# Elektriskeem.net
KiCad netlist of a schematic drawn in Altium Designer
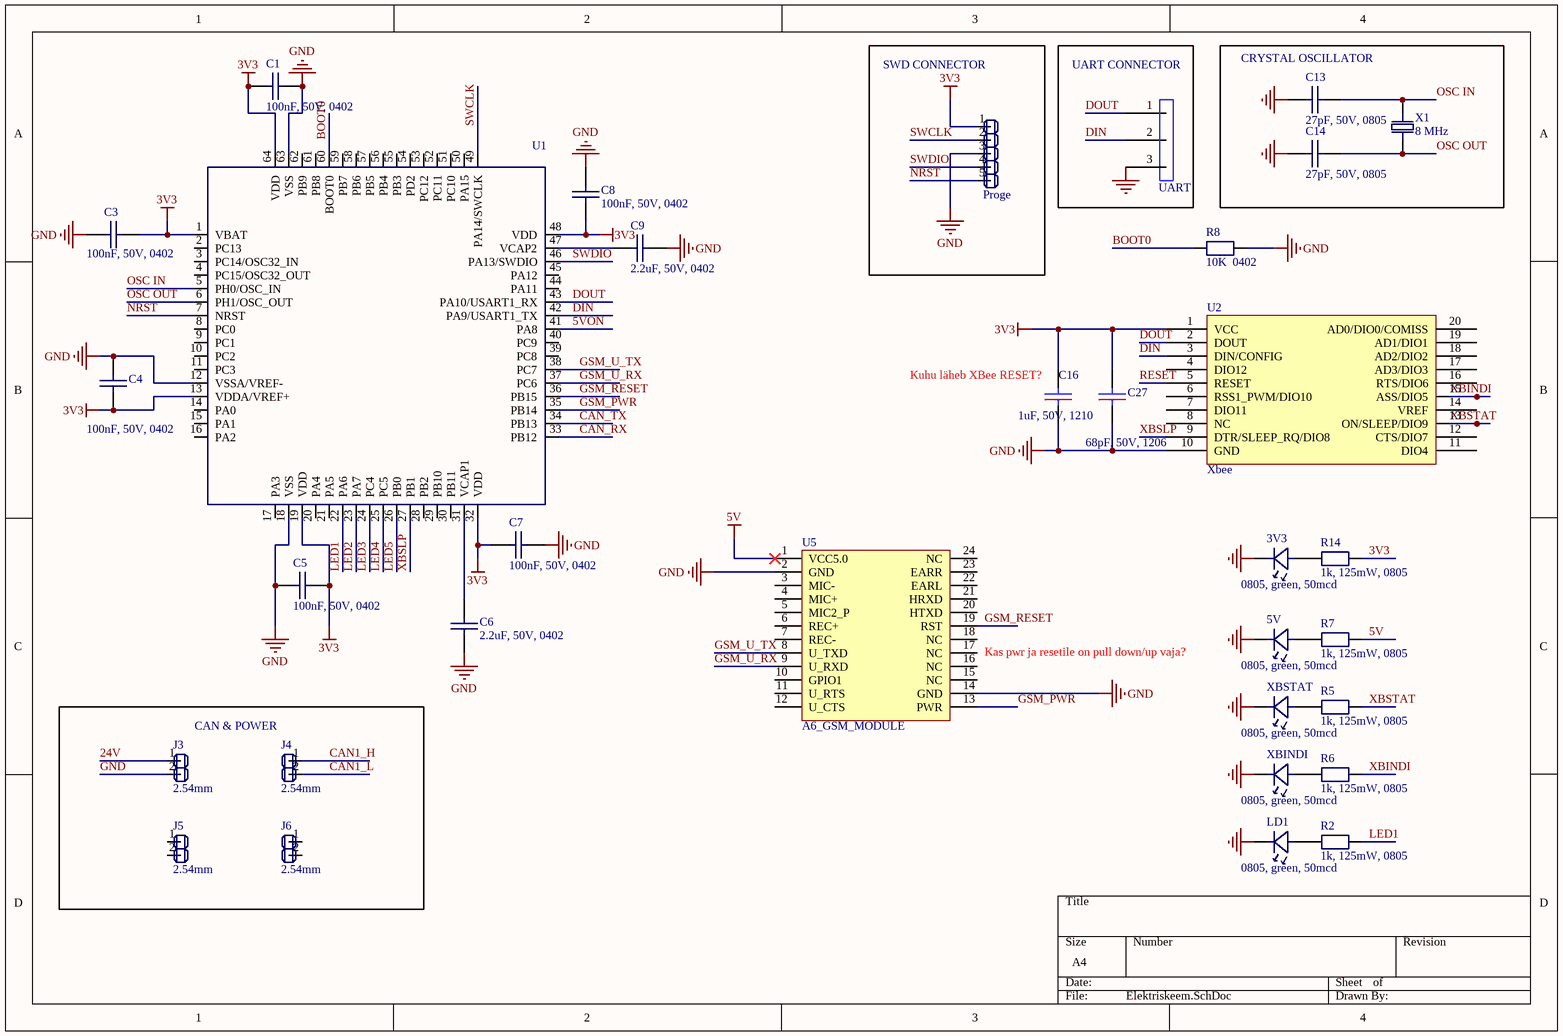
[diagram p0: Elektriskeem.SchDoc]

(export (version "E")
  (design (tool "Eeschema 10.0.6"))
  (components
    (comp (ref "3V3")
      (value "0805, green, 50mcd")
      (footprint "LED2012X06N")
      (description "Cathode (-) marked by silkscreen line")
      (fields (field (name "MANUFACTURER") "KINGBRIGHT"))
      (libsource (lib "AS_component_library") (part "LED"))
    )
    (comp (ref "5V")
      (value "0805, green, 50mcd")
      (footprint "LED2012X06N")
      (description "Cathode (-) marked by silkscreen line")
      (fields (field (name "MANUFACTURER") "KINGBRIGHT"))
      (libsource (lib "AS_component_library") (part "LED"))
    )
    (comp (ref "C1")
      (value "100nF, 50V, 0402")
      (footprint "1005 [0402] CAP")
      (libsource (lib "AS_component_library") (part "Capacitor"))
    )
    (comp (ref "C3")
      (value "100nF, 50V, 0402")
      (footprint "1005 [0402] CAP")
      (libsource (lib "AS_component_library") (part "Capacitor"))
    )
    (comp (ref "C4")
      (value "100nF, 50V, 0402")
      (footprint "1005 [0402] CAP")
      (libsource (lib "AS_component_library") (part "Capacitor"))
    )
    (comp (ref "C5")
      (value "100nF, 50V, 0402")
      (footprint "1005 [0402] CAP")
      (libsource (lib "AS_component_library") (part "Capacitor"))
    )
    (comp (ref "C6")
      (value "2.2uF, 50V, 0402")
      (footprint "1005 [0402] CAP")
      (libsource (lib "AS_component_library") (part "Capacitor"))
    )
    (comp (ref "C7")
      (value "100nF, 50V, 0402")
      (footprint "1005 [0402] CAP")
      (libsource (lib "AS_component_library") (part "Capacitor"))
    )
    (comp (ref "C8")
      (value "100nF, 50V, 0402")
      (footprint "1005 [0402] CAP")
      (libsource (lib "AS_component_library") (part "Capacitor"))
    )
    (comp (ref "C9")
      (value "2.2uF, 50V, 0402")
      (footprint "1005 [0402] CAP")
      (libsource (lib "AS_component_library") (part "Capacitor"))
    )
    (comp (ref "C13")
      (value "27pF, 50V, 0805")
      (footprint "2012 [0805] CAP")
      (fields (field (name "MANUFACTURER") "KEMET"))
      (libsource (lib "AS_component_library") (part "Capacitor"))
    )
    (comp (ref "C14")
      (value "27pF, 50V, 0805")
      (footprint "2012 [0805] CAP")
      (fields (field (name "MANUFACTURER") "KEMET"))
      (libsource (lib "AS_component_library") (part "Capacitor"))
    )
    (comp (ref "C16")
      (value "1uF, 50V, 1210")
      (footprint "3225 [1210] CAP")
      (libsource (lib "AS_component_library") (part "Capacitor"))
    )
    (comp (ref "C27")
      (value "68pF, 50V, 1206")
      (footprint "3216 [1206] CAP")
      (libsource (lib "5VTO3V3") (part "Capacitor"))
    )
    (comp (ref "J3")
      (value "2.54mm")
      (footprint "Pin Header 2x1")
      (libsource (lib "AS_component_library") (part "Pin Header 2x1"))
    )
    (comp (ref "J4")
      (value "2.54mm")
      (footprint "Pin Header 2x1")
      (libsource (lib "AS_component_library") (part "Pin Header 2x1"))
    )
    (comp (ref "J5")
      (value "2.54mm")
      (footprint "Pin Header 2x1")
      (libsource (lib "AS_component_library") (part "Pin Header 2x1"))
    )
    (comp (ref "J6")
      (value "2.54mm")
      (footprint "Pin Header 2x1")
      (libsource (lib "AS_component_library") (part "Pin Header 2x1"))
    )
    (comp (ref "LD1")
      (value "0805, green, 50mcd")
      (footprint "LED2012X06N")
      (description "Cathode (-) marked by silkscreen line")
      (fields (field (name "MANUFACTURER") "KINGBRIGHT"))
      (libsource (lib "AS_component_library") (part "LED"))
    )
    (comp (ref "Proge")
      (value "Pin Header 5x1")
      (footprint "Pin Header 5x1")
      (fields (field (name "MANUFACTURER") "TE CONNECTIVITY"))
      (libsource (lib "AS_component_library") (part "Pin Header 5x1"))
    )
    (comp (ref "R2")
      (value "1k, 125mW, 0805")
      (footprint "2012 [0805] RES")
      (fields (field (name "MANUFACTURER") "VISHAY DRALORIC"))
      (libsource (lib "AS_component_library") (part "Resistor"))
    )
    (comp (ref "R5")
      (value "1k, 125mW, 0805")
      (footprint "2012 [0805] RES")
      (fields (field (name "MANUFACTURER") "VISHAY DRALORIC"))
      (libsource (lib "AS_component_library") (part "Resistor"))
    )
    (comp (ref "R6")
      (value "1k, 125mW, 0805")
      (footprint "2012 [0805] RES")
      (fields (field (name "MANUFACTURER") "VISHAY DRALORIC"))
      (libsource (lib "AS_component_library") (part "Resistor"))
    )
    (comp (ref "R7")
      (value "1k, 125mW, 0805")
      (footprint "2012 [0805] RES")
      (fields (field (name "MANUFACTURER") "VISHAY DRALORIC"))
      (libsource (lib "AS_component_library") (part "Resistor"))
    )
    (comp (ref "R8")
      (value "10K  0402")
      (footprint "1005 [0402] RES")
      (libsource (lib "AS_component_library") (part "Resistor"))
    )
    (comp (ref "R14")
      (value "1k, 125mW, 0805")
      (footprint "2012 [0805] RES")
      (fields (field (name "MANUFACTURER") "VISHAY DRALORIC"))
      (libsource (lib "AS_component_library") (part "Resistor"))
    )
    (comp (ref "U1")
      (value "STM32F4 64-pin")
      (footprint "LQFP64")
      (fields (field (name "MANUFACTURER") "STMICROELECTRONICS"))
      (libsource (lib "AS_component_library") (part "STM32F4 64-pin"))
    )
    (comp (ref "U2") (value "Xbee") (footprint "XBEE - duplicate1") (libsource (lib "xbee") (part "Xbee")))
    (comp (ref "U5")
      (value "A6_GSM_MODULE")
      (footprint "A6_gsm_module")
      (libsource (lib "telemetry_component_lib") (part "A6_GSM_MODULE"))
    )
    (comp (ref "UART")
      (value "Pin Header 3x1")
      (footprint "Pin Header 3x1")
      (libsource (lib "AS_component_library") (part "Pin Header 3x1"))
    )
    (comp (ref "X1")
      (value "8 MHz")
      (footprint "5.0x3.2 SMD Crystal")
      (fields (field (name "MANUFACTURER") "ABRACON"))
      (libsource (lib "AS_component_library") (part "Crystal"))
    )
    (comp (ref "XBINDI")
      (value "0805, green, 50mcd")
      (footprint "LED2012X06N")
      (description "Cathode (-) marked by silkscreen line")
      (fields (field (name "MANUFACTURER") "KINGBRIGHT"))
      (libsource (lib "AS_component_library") (part "LED"))
    )
    (comp (ref "XBSTAT")
      (value "0805, green, 50mcd")
      (footprint "LED2012X06N")
      (description "Cathode (-) marked by silkscreen line")
      (fields (field (name "MANUFACTURER") "KINGBRIGHT"))
      (libsource (lib "AS_component_library") (part "LED"))
    )
  )
  (nets
    (net (code "1") (name "/5VON") (class "Default")
      (node (ref "U1") (pin "41") (pinfunction "PA8_41") (pintype "passive"))
    )
    (net (code "2") (name "/24V") (class "Default")
      (node (ref "J3") (pin "1") (pinfunction "1_1") (pintype "passive"))
    )
    (net (code "3") (name "/BOOT0") (class "Default")
      (node (ref "R8") (pin "1") (pinfunction "1_1") (pintype "passive"))
      (node (ref "U1") (pin "60") (pinfunction "BOOT0_60") (pintype "passive"))
    )
    (net (code "4") (name "/CAN1_H") (class "Default")
      (node (ref "J4") (pin "1") (pinfunction "1_1") (pintype "passive"))
    )
    (net (code "5") (name "/CAN1_L") (class "Default")
      (node (ref "J4") (pin "2") (pinfunction "2_2") (pintype "passive"))
    )
    (net (code "6") (name "/CAN_RX") (class "Default")
      (node (ref "U1") (pin "33") (pinfunction "PB12_33") (pintype "passive"))
    )
    (net (code "7") (name "/CAN_TX") (class "Default")
      (node (ref "U1") (pin "34") (pinfunction "PB13_34") (pintype "passive"))
    )
    (net (code "8") (name "/DIN") (class "Default")
      (node (ref "U1") (pin "42") (pinfunction "PA9/USART1_TX_42") (pintype "passive"))
      (node (ref "U2") (pin "3") (pinfunction "DIN/CONFIG_3") (pintype "passive"))
      (node (ref "UART") (pin "2") (pinfunction "2_2") (pintype "passive"))
    )
    (net (code "9") (name "/DOUT") (class "Default")
      (node (ref "U1") (pin "43") (pinfunction "PA10/USART1_RX_43") (pintype "passive"))
      (node (ref "U2") (pin "2") (pinfunction "DOUT_2") (pintype "passive"))
      (node (ref "UART") (pin "1") (pinfunction "1_1") (pintype "passive"))
    )
    (net (code "10") (name "/GSM_PWR") (class "Default")
      (node (ref "U1") (pin "35") (pinfunction "PB14_35") (pintype "passive"))
      (node (ref "U5") (pin "13") (pinfunction "PWR_13") (pintype "passive"))
    )
    (net (code "11") (name "/GSM_RESET") (class "Default")
      (node (ref "U1") (pin "36") (pinfunction "PB15_36") (pintype "passive"))
      (node (ref "U5") (pin "19") (pinfunction "RST_19") (pintype "passive"))
    )
    (net (code "12") (name "/GSM_U_RX") (class "Default")
      (node (ref "U1") (pin "37") (pinfunction "PC6_37") (pintype "passive"))
      (node (ref "U5") (pin "9") (pinfunction "U_RXD_9") (pintype "passive"))
    )
    (net (code "13") (name "/GSM_U_TX") (class "Default")
      (node (ref "U1") (pin "38") (pinfunction "PC7_38") (pintype "passive"))
      (node (ref "U5") (pin "8") (pinfunction "U_TXD_8") (pintype "passive"))
    )
    (net (code "14") (name "/LED1") (class "Default")
      (node (ref "R2") (pin "2") (pinfunction "2_2") (pintype "passive"))
      (node (ref "U1") (pin "22") (pinfunction "PA6_22") (pintype "passive"))
    )
    (net (code "15") (name "/LED2") (class "Default")
      (node (ref "U1") (pin "23") (pinfunction "PA7_23") (pintype "passive"))
    )
    (net (code "16") (name "/LED3") (class "Default")
      (node (ref "U1") (pin "24") (pinfunction "PC4_24") (pintype "passive"))
    )
    (net (code "17") (name "/LED4") (class "Default")
      (node (ref "U1") (pin "25") (pinfunction "PC5_25") (pintype "passive"))
    )
    (net (code "18") (name "/LED5") (class "Default")
      (node (ref "U1") (pin "26") (pinfunction "PB0_26") (pintype "passive"))
    )
    (net (code "19") (name "/NRST") (class "Default")
      (node (ref "Proge") (pin "5") (pinfunction "5_5") (pintype "passive"))
      (node (ref "U1") (pin "7") (pinfunction "NRST_7") (pintype "passive"))
    )
    (net (code "20") (name "/OSC IN") (class "Default")
      (node (ref "C13") (pin "1") (pinfunction "1_1") (pintype "passive"))
      (node (ref "U1") (pin "5") (pinfunction "PH0/OSC_IN_5") (pintype "passive"))
      (node (ref "X1") (pin "1") (pinfunction "1_1") (pintype "passive"))
    )
    (net (code "21") (name "/OSC OUT") (class "Default")
      (node (ref "C14") (pin "2") (pinfunction "2_2") (pintype "passive"))
      (node (ref "U1") (pin "6") (pinfunction "PH1/OSC_OUT_6") (pintype "passive"))
      (node (ref "X1") (pin "2") (pinfunction "2_2") (pintype "passive"))
    )
    (net (code "22") (name "/RESET") (class "Default")
      (node (ref "U2") (pin "5") (pinfunction "RESET_5") (pintype "passive"))
    )
    (net (code "23") (name "/SWCLK") (class "Default")
      (node (ref "Proge") (pin "2") (pinfunction "2_2") (pintype "passive"))
      (node (ref "U1") (pin "49") (pinfunction "PA14/SWCLK_49") (pintype "passive"))
    )
    (net (code "24") (name "/SWDIO") (class "Default")
      (node (ref "Proge") (pin "4") (pinfunction "4_4") (pintype "passive"))
      (node (ref "U1") (pin "46") (pinfunction "PA13/SWDIO_46") (pintype "passive"))
    )
    (net (code "25") (name "/XBINDI") (class "Default")
      (node (ref "R6") (pin "2") (pinfunction "2_2") (pintype "passive"))
      (node (ref "U2") (pin "15") (pinfunction "ASS/DIO5_15") (pintype "passive"))
    )
    (net (code "26") (name "/XBSLP") (class "Default")
      (node (ref "U1") (pin "27") (pinfunction "PB1_27") (pintype "passive"))
      (node (ref "U2") (pin "9") (pinfunction "DTR/SLEEP_RQ/DIO8_9") (pintype "passive"))
    )
    (net (code "27") (name "/XBSTAT") (class "Default")
      (node (ref "R5") (pin "2") (pinfunction "2_2") (pintype "passive"))
      (node (ref "U2") (pin "13") (pinfunction "ON/SLEEP/DIO9_13") (pintype "passive"))
    )
    (net (code "28") (name "3V3") (class "Default")
      (node (ref "C1") (pin "2") (pinfunction "2_2") (pintype "passive"))
      (node (ref "C16") (pin "1") (pinfunction "1_1") (pintype "passive"))
      (node (ref "C27") (pin "1") (pinfunction "1_1") (pintype "passive"))
      (node (ref "C3") (pin "1") (pinfunction "1_1") (pintype "passive"))
      (node (ref "C4") (pin "2") (pinfunction "2_2") (pintype "passive"))
      (node (ref "C5") (pin "1") (pinfunction "1_1") (pintype "passive"))
      (node (ref "C7") (pin "2") (pinfunction "2_2") (pintype "passive"))
      (node (ref "C8") (pin "2") (pinfunction "2_2") (pintype "passive"))
      (node (ref "Proge") (pin "1") (pinfunction "1_1") (pintype "passive"))
      (node (ref "R14") (pin "2") (pinfunction "2_2") (pintype "passive"))
      (node (ref "U1") (pin "1") (pinfunction "VBAT_1") (pintype "passive"))
      (node (ref "U1") (pin "13") (pinfunction "VDDA/VREF+_13") (pintype "passive"))
      (node (ref "U1") (pin "19") (pinfunction "VDD_19") (pintype "passive"))
      (node (ref "U1") (pin "32") (pinfunction "VDD_32") (pintype "passive"))
      (node (ref "U1") (pin "48") (pinfunction "VDD_48") (pintype "passive"))
      (node (ref "U1") (pin "64") (pinfunction "VDD_64") (pintype "passive"))
      (node (ref "U2") (pin "1") (pinfunction "VCC_1") (pintype "passive"))
    )
    (net (code "29") (name "5V") (class "Default")
      (node (ref "R7") (pin "2") (pinfunction "2_2") (pintype "passive"))
      (node (ref "U5") (pin "1") (pinfunction "VCC5.0_1") (pintype "passive"))
    )
    (net (code "30") (name "GND") (class "Default")
      (node (ref "3V3") (pin "1") (pinfunction "1_1") (pintype "passive"))
      (node (ref "5V") (pin "1") (pinfunction "1_1") (pintype "passive"))
      (node (ref "C1") (pin "1") (pinfunction "1_1") (pintype "passive"))
      (node (ref "C13") (pin "2") (pinfunction "2_2") (pintype "passive"))
      (node (ref "C14") (pin "1") (pinfunction "1_1") (pintype "passive"))
      (node (ref "C16") (pin "2") (pinfunction "2_2") (pintype "passive"))
      (node (ref "C27") (pin "2") (pinfunction "2_2") (pintype "passive"))
      (node (ref "C3") (pin "2") (pinfunction "2_2") (pintype "passive"))
      (node (ref "C4") (pin "1") (pinfunction "1_1") (pintype "passive"))
      (node (ref "C5") (pin "2") (pinfunction "2_2") (pintype "passive"))
      (node (ref "C6") (pin "2") (pinfunction "2_2") (pintype "passive"))
      (node (ref "C7") (pin "1") (pinfunction "1_1") (pintype "passive"))
      (node (ref "C8") (pin "1") (pinfunction "1_1") (pintype "passive"))
      (node (ref "C9") (pin "1") (pinfunction "1_1") (pintype "passive"))
      (node (ref "J3") (pin "2") (pinfunction "2_2") (pintype "passive"))
      (node (ref "LD1") (pin "1") (pinfunction "1_1") (pintype "passive"))
      (node (ref "Proge") (pin "3") (pinfunction "3_3") (pintype "passive"))
      (node (ref "R8") (pin "2") (pinfunction "2_2") (pintype "passive"))
      (node (ref "U1") (pin "12") (pinfunction "VSSA/VREF-_12") (pintype "passive"))
      (node (ref "U1") (pin "18") (pinfunction "VSS_18") (pintype "passive"))
      (node (ref "U1") (pin "63") (pinfunction "VSS_63") (pintype "passive"))
      (node (ref "U2") (pin "10") (pinfunction "GND_10") (pintype "passive"))
      (node (ref "U5") (pin "14") (pinfunction "GND_14") (pintype "passive"))
      (node (ref "U5") (pin "2") (pinfunction "GND_2") (pintype "passive"))
      (node (ref "UART") (pin "3") (pinfunction "3_3") (pintype "passive"))
      (node (ref "XBINDI") (pin "1") (pinfunction "1_1") (pintype "passive"))
      (node (ref "XBSTAT") (pin "1") (pinfunction "1_1") (pintype "passive"))
    )
    (net (code "31") (name "Net-(3V3-Pad2)") (class "Default")
      (node (ref "3V3") (pin "2") (pinfunction "2_2") (pintype "passive"))
      (node (ref "R14") (pin "1") (pinfunction "1_1") (pintype "passive"))
    )
    (net (code "32") (name "Net-(5V-Pad2)") (class "Default")
      (node (ref "5V") (pin "2") (pinfunction "2_2") (pintype "passive"))
      (node (ref "R7") (pin "1") (pinfunction "1_1") (pintype "passive"))
    )
    (net (code "33") (name "Net-(LD1-Pad2)") (class "Default")
      (node (ref "LD1") (pin "2") (pinfunction "2_2") (pintype "passive"))
      (node (ref "R2") (pin "1") (pinfunction "1_1") (pintype "passive"))
    )
    (net (code "34") (name "Net-(R5-Pad1)") (class "Default")
      (node (ref "R5") (pin "1") (pinfunction "1_1") (pintype "passive"))
      (node (ref "XBSTAT") (pin "2") (pinfunction "2_2") (pintype "passive"))
    )
    (net (code "35") (name "Net-(R6-Pad1)") (class "Default")
      (node (ref "R6") (pin "1") (pinfunction "1_1") (pintype "passive"))
      (node (ref "XBINDI") (pin "2") (pinfunction "2_2") (pintype "passive"))
    )
    (net (code "36") (name "Net-(U1-VCAP1)") (class "Default")
      (node (ref "C6") (pin "1") (pinfunction "1_1") (pintype "passive"))
      (node (ref "U1") (pin "31") (pinfunction "VCAP1_31") (pintype "passive"))
    )
    (net (code "37") (name "Net-(U1-VCAP2)") (class "Default")
      (node (ref "C9") (pin "2") (pinfunction "2_2") (pintype "passive"))
      (node (ref "U1") (pin "47") (pinfunction "VCAP2_47") (pintype "passive"))
    )
    (net (code "38") (name "unconnected-(J5-Pad1)") (class "Default")
      (node (ref "J5") (pin "1") (pinfunction "1_1") (pintype "passive"))
    )
    (net (code "39") (name "unconnected-(J5-Pad2)") (class "Default")
      (node (ref "J5") (pin "2") (pinfunction "2_2") (pintype "passive"))
    )
    (net (code "40") (name "unconnected-(J6-Pad1)") (class "Default")
      (node (ref "J6") (pin "1") (pinfunction "1_1") (pintype "passive"))
    )
    (net (code "41") (name "unconnected-(J6-Pad2)") (class "Default")
      (node (ref "J6") (pin "2") (pinfunction "2_2") (pintype "passive"))
    )
    (net (code "42") (name "unconnected-(U1-PA0-Pad14)") (class "Default")
      (node (ref "U1") (pin "14") (pinfunction "PA0_14") (pintype "passive"))
    )
    (net (code "43") (name "unconnected-(U1-PA1-Pad15)") (class "Default")
      (node (ref "U1") (pin "15") (pinfunction "PA1_15") (pintype "passive"))
    )
    (net (code "44") (name "unconnected-(U1-PA2-Pad16)") (class "Default")
      (node (ref "U1") (pin "16") (pinfunction "PA2_16") (pintype "passive"))
    )
    (net (code "45") (name "unconnected-(U1-PA3-Pad17)") (class "Default")
      (node (ref "U1") (pin "17") (pinfunction "PA3_17") (pintype "passive"))
    )
    (net (code "46") (name "unconnected-(U1-PA4-Pad20)") (class "Default")
      (node (ref "U1") (pin "20") (pinfunction "PA4_20") (pintype "passive"))
    )
    (net (code "47") (name "unconnected-(U1-PA5-Pad21)") (class "Default")
      (node (ref "U1") (pin "21") (pinfunction "PA5_21") (pintype "passive"))
    )
    (net (code "48") (name "unconnected-(U1-PA11-Pad44)") (class "Default")
      (node (ref "U1") (pin "44") (pinfunction "PA11_44") (pintype "passive"))
    )
    (net (code "49") (name "unconnected-(U1-PA12-Pad45)") (class "Default")
      (node (ref "U1") (pin "45") (pinfunction "PA12_45") (pintype "passive"))
    )
    (net (code "50") (name "unconnected-(U1-PA15-Pad50)") (class "Default")
      (node (ref "U1") (pin "50") (pinfunction "PA15_50") (pintype "passive"))
    )
    (net (code "51") (name "unconnected-(U1-PB2-Pad28)") (class "Default")
      (node (ref "U1") (pin "28") (pinfunction "PB2_28") (pintype "passive"))
    )
    (net (code "52") (name "unconnected-(U1-PB3-Pad55)") (class "Default")
      (node (ref "U1") (pin "55") (pinfunction "PB3_55") (pintype "passive"))
    )
    (net (code "53") (name "unconnected-(U1-PB4-Pad56)") (class "Default")
      (node (ref "U1") (pin "56") (pinfunction "PB4_56") (pintype "passive"))
    )
    (net (code "54") (name "unconnected-(U1-PB5-Pad57)") (class "Default")
      (node (ref "U1") (pin "57") (pinfunction "PB5_57") (pintype "passive"))
    )
    (net (code "55") (name "unconnected-(U1-PB6-Pad58)") (class "Default")
      (node (ref "U1") (pin "58") (pinfunction "PB6_58") (pintype "passive"))
    )
    (net (code "56") (name "unconnected-(U1-PB7-Pad59)") (class "Default")
      (node (ref "U1") (pin "59") (pinfunction "PB7_59") (pintype "passive"))
    )
    (net (code "57") (name "unconnected-(U1-PB8-Pad61)") (class "Default")
      (node (ref "U1") (pin "61") (pinfunction "PB8_61") (pintype "passive"))
    )
    (net (code "58") (name "unconnected-(U1-PB9-Pad62)") (class "Default")
      (node (ref "U1") (pin "62") (pinfunction "PB9_62") (pintype "passive"))
    )
    (net (code "59") (name "unconnected-(U1-PB10-Pad29)") (class "Default")
      (node (ref "U1") (pin "29") (pinfunction "PB10_29") (pintype "passive"))
    )
    (net (code "60") (name "unconnected-(U1-PB11-Pad30)") (class "Default")
      (node (ref "U1") (pin "30") (pinfunction "PB11_30") (pintype "passive"))
    )
    (net (code "61") (name "unconnected-(U1-PC0-Pad8)") (class "Default")
      (node (ref "U1") (pin "8") (pinfunction "PC0_8") (pintype "passive"))
    )
    (net (code "62") (name "unconnected-(U1-PC1-Pad9)") (class "Default")
      (node (ref "U1") (pin "9") (pinfunction "PC1_9") (pintype "passive"))
    )
    (net (code "63") (name "unconnected-(U1-PC2-Pad10)") (class "Default")
      (node (ref "U1") (pin "10") (pinfunction "PC2_10") (pintype "passive"))
    )
    (net (code "64") (name "unconnected-(U1-PC3-Pad11)") (class "Default")
      (node (ref "U1") (pin "11") (pinfunction "PC3_11") (pintype "passive"))
    )
    (net (code "65") (name "unconnected-(U1-PC8-Pad39)") (class "Default")
      (node (ref "U1") (pin "39") (pinfunction "PC8_39") (pintype "passive"))
    )
    (net (code "66") (name "unconnected-(U1-PC9-Pad40)") (class "Default")
      (node (ref "U1") (pin "40") (pinfunction "PC9_40") (pintype "passive"))
    )
    (net (code "67") (name "unconnected-(U1-PC10-Pad51)") (class "Default")
      (node (ref "U1") (pin "51") (pinfunction "PC10_51") (pintype "passive"))
    )
    (net (code "68") (name "unconnected-(U1-PC11-Pad52)") (class "Default")
      (node (ref "U1") (pin "52") (pinfunction "PC11_52") (pintype "passive"))
    )
    (net (code "69") (name "unconnected-(U1-PC12-Pad53)") (class "Default")
      (node (ref "U1") (pin "53") (pinfunction "PC12_53") (pintype "passive"))
    )
    (net (code "70") (name "unconnected-(U1-PC13-Pad2)") (class "Default")
      (node (ref "U1") (pin "2") (pinfunction "PC13_2") (pintype "passive"))
    )
    (net (code "71") (name "unconnected-(U1-PC14{slash}OSC32_IN-Pad3)") (class "Default")
      (node (ref "U1") (pin "3") (pinfunction "PC14/OSC32_IN_3") (pintype "passive"))
    )
    (net (code "72") (name "unconnected-(U1-PC15{slash}OSC32_OUT-Pad4)") (class "Default")
      (node (ref "U1") (pin "4") (pinfunction "PC15/OSC32_OUT_4") (pintype "passive"))
    )
    (net (code "73") (name "unconnected-(U1-PD2-Pad54)") (class "Default")
      (node (ref "U1") (pin "54") (pinfunction "PD2_54") (pintype "passive"))
    )
    (net (code "74") (name "unconnected-(U2-AD0{slash}DIO0{slash}COMISS-Pad20)") (class "Default")
      (node (ref "U2") (pin "20") (pinfunction "AD0/DIO0/COMISS_20") (pintype "passive"))
    )
    (net (code "75") (name "unconnected-(U2-AD1{slash}DIO1-Pad19)") (class "Default")
      (node (ref "U2") (pin "19") (pinfunction "AD1/DIO1_19") (pintype "passive"))
    )
    (net (code "76") (name "unconnected-(U2-AD2{slash}DIO2-Pad18)") (class "Default")
      (node (ref "U2") (pin "18") (pinfunction "AD2/DIO2_18") (pintype "passive"))
    )
    (net (code "77") (name "unconnected-(U2-AD3{slash}DIO3-Pad17)") (class "Default")
      (node (ref "U2") (pin "17") (pinfunction "AD3/DIO3_17") (pintype "passive"))
    )
    (net (code "78") (name "unconnected-(U2-CTS{slash}DIO7-Pad12)") (class "Default")
      (node (ref "U2") (pin "12") (pinfunction "CTS/DIO7_12") (pintype "passive"))
    )
    (net (code "79") (name "unconnected-(U2-DIO4-Pad11)") (class "Default")
      (node (ref "U2") (pin "11") (pinfunction "DIO4_11") (pintype "passive"))
    )
    (net (code "80") (name "unconnected-(U2-DIO11-Pad7)") (class "Default")
      (node (ref "U2") (pin "7") (pinfunction "DIO11_7") (pintype "passive"))
    )
    (net (code "81") (name "unconnected-(U2-DIO12-Pad4)") (class "Default")
      (node (ref "U2") (pin "4") (pinfunction "DIO12_4") (pintype "passive"))
    )
    (net (code "82") (name "unconnected-(U2-NC-Pad8)") (class "Default")
      (node (ref "U2") (pin "8") (pinfunction "NC_8") (pintype "passive"))
    )
    (net (code "83") (name "unconnected-(U2-RSS1_PWM{slash}DIO10-Pad6)") (class "Default")
      (node (ref "U2") (pin "6") (pinfunction "RSS1_PWM/DIO10_6") (pintype "passive"))
    )
    (net (code "84") (name "unconnected-(U2-RTS{slash}DIO6-Pad16)") (class "Default")
      (node (ref "U2") (pin "16") (pinfunction "RTS/DIO6_16") (pintype "passive"))
    )
    (net (code "85") (name "unconnected-(U2-VREF-Pad14)") (class "Default")
      (node (ref "U2") (pin "14") (pinfunction "VREF_14") (pintype "passive"))
    )
    (net (code "86") (name "unconnected-(U5-EARL-Pad22)") (class "Default")
      (node (ref "U5") (pin "22") (pinfunction "EARL_22") (pintype "passive"))
    )
    (net (code "87") (name "unconnected-(U5-EARR-Pad23)") (class "Default")
      (node (ref "U5") (pin "23") (pinfunction "EARR_23") (pintype "passive"))
    )
    (net (code "88") (name "unconnected-(U5-GPIO1-Pad10)") (class "Default")
      (node (ref "U5") (pin "10") (pinfunction "GPIO1_10") (pintype "passive"))
    )
    (net (code "89") (name "unconnected-(U5-HRXD-Pad21)") (class "Default")
      (node (ref "U5") (pin "21") (pinfunction "HRXD_21") (pintype "passive"))
    )
    (net (code "90") (name "unconnected-(U5-HTXD-Pad20)") (class "Default")
      (node (ref "U5") (pin "20") (pinfunction "HTXD_20") (pintype "passive"))
    )
    (net (code "91") (name "unconnected-(U5-MIC+-Pad4)") (class "Default")
      (node (ref "U5") (pin "4") (pinfunction "MIC+_4") (pintype "passive"))
    )
    (net (code "92") (name "unconnected-(U5-MIC--Pad3)") (class "Default")
      (node (ref "U5") (pin "3") (pinfunction "MIC-_3") (pintype "passive"))
    )
    (net (code "93") (name "unconnected-(U5-MIC2_P-Pad5)") (class "Default")
      (node (ref "U5") (pin "5") (pinfunction "MIC2_P_5") (pintype "passive"))
    )
    (net (code "94") (name "unconnected-(U5-NC-Pad15)") (class "Default")
      (node (ref "U5") (pin "15") (pinfunction "NC_15") (pintype "passive"))
    )
    (net (code "95") (name "unconnected-(U5-NC-Pad16)") (class "Default")
      (node (ref "U5") (pin "16") (pinfunction "NC_16") (pintype "passive"))
    )
    (net (code "96") (name "unconnected-(U5-NC-Pad17)") (class "Default")
      (node (ref "U5") (pin "17") (pinfunction "NC_17") (pintype "passive"))
    )
    (net (code "97") (name "unconnected-(U5-NC-Pad18)") (class "Default")
      (node (ref "U5") (pin "18") (pinfunction "NC_18") (pintype "passive"))
    )
    (net (code "98") (name "unconnected-(U5-NC-Pad24)") (class "Default")
      (node (ref "U5") (pin "24") (pinfunction "NC_24") (pintype "passive"))
    )
    (net (code "99") (name "unconnected-(U5-REC+-Pad6)") (class "Default")
      (node (ref "U5") (pin "6") (pinfunction "REC+_6") (pintype "passive"))
    )
    (net (code "100") (name "unconnected-(U5-REC--Pad7)") (class "Default")
      (node (ref "U5") (pin "7") (pinfunction "REC-_7") (pintype "passive"))
    )
    (net (code "101") (name "unconnected-(U5-U_CTS-Pad12)") (class "Default")
      (node (ref "U5") (pin "12") (pinfunction "U_CTS_12") (pintype "passive"))
    )
    (net (code "102") (name "unconnected-(U5-U_RTS-Pad11)") (class "Default")
      (node (ref "U5") (pin "11") (pinfunction "U_RTS_11") (pintype "passive"))
    )
  )
)
